# Schem_WS_v4.net
KiCad netlist of a schematic drawn in Altium Designer
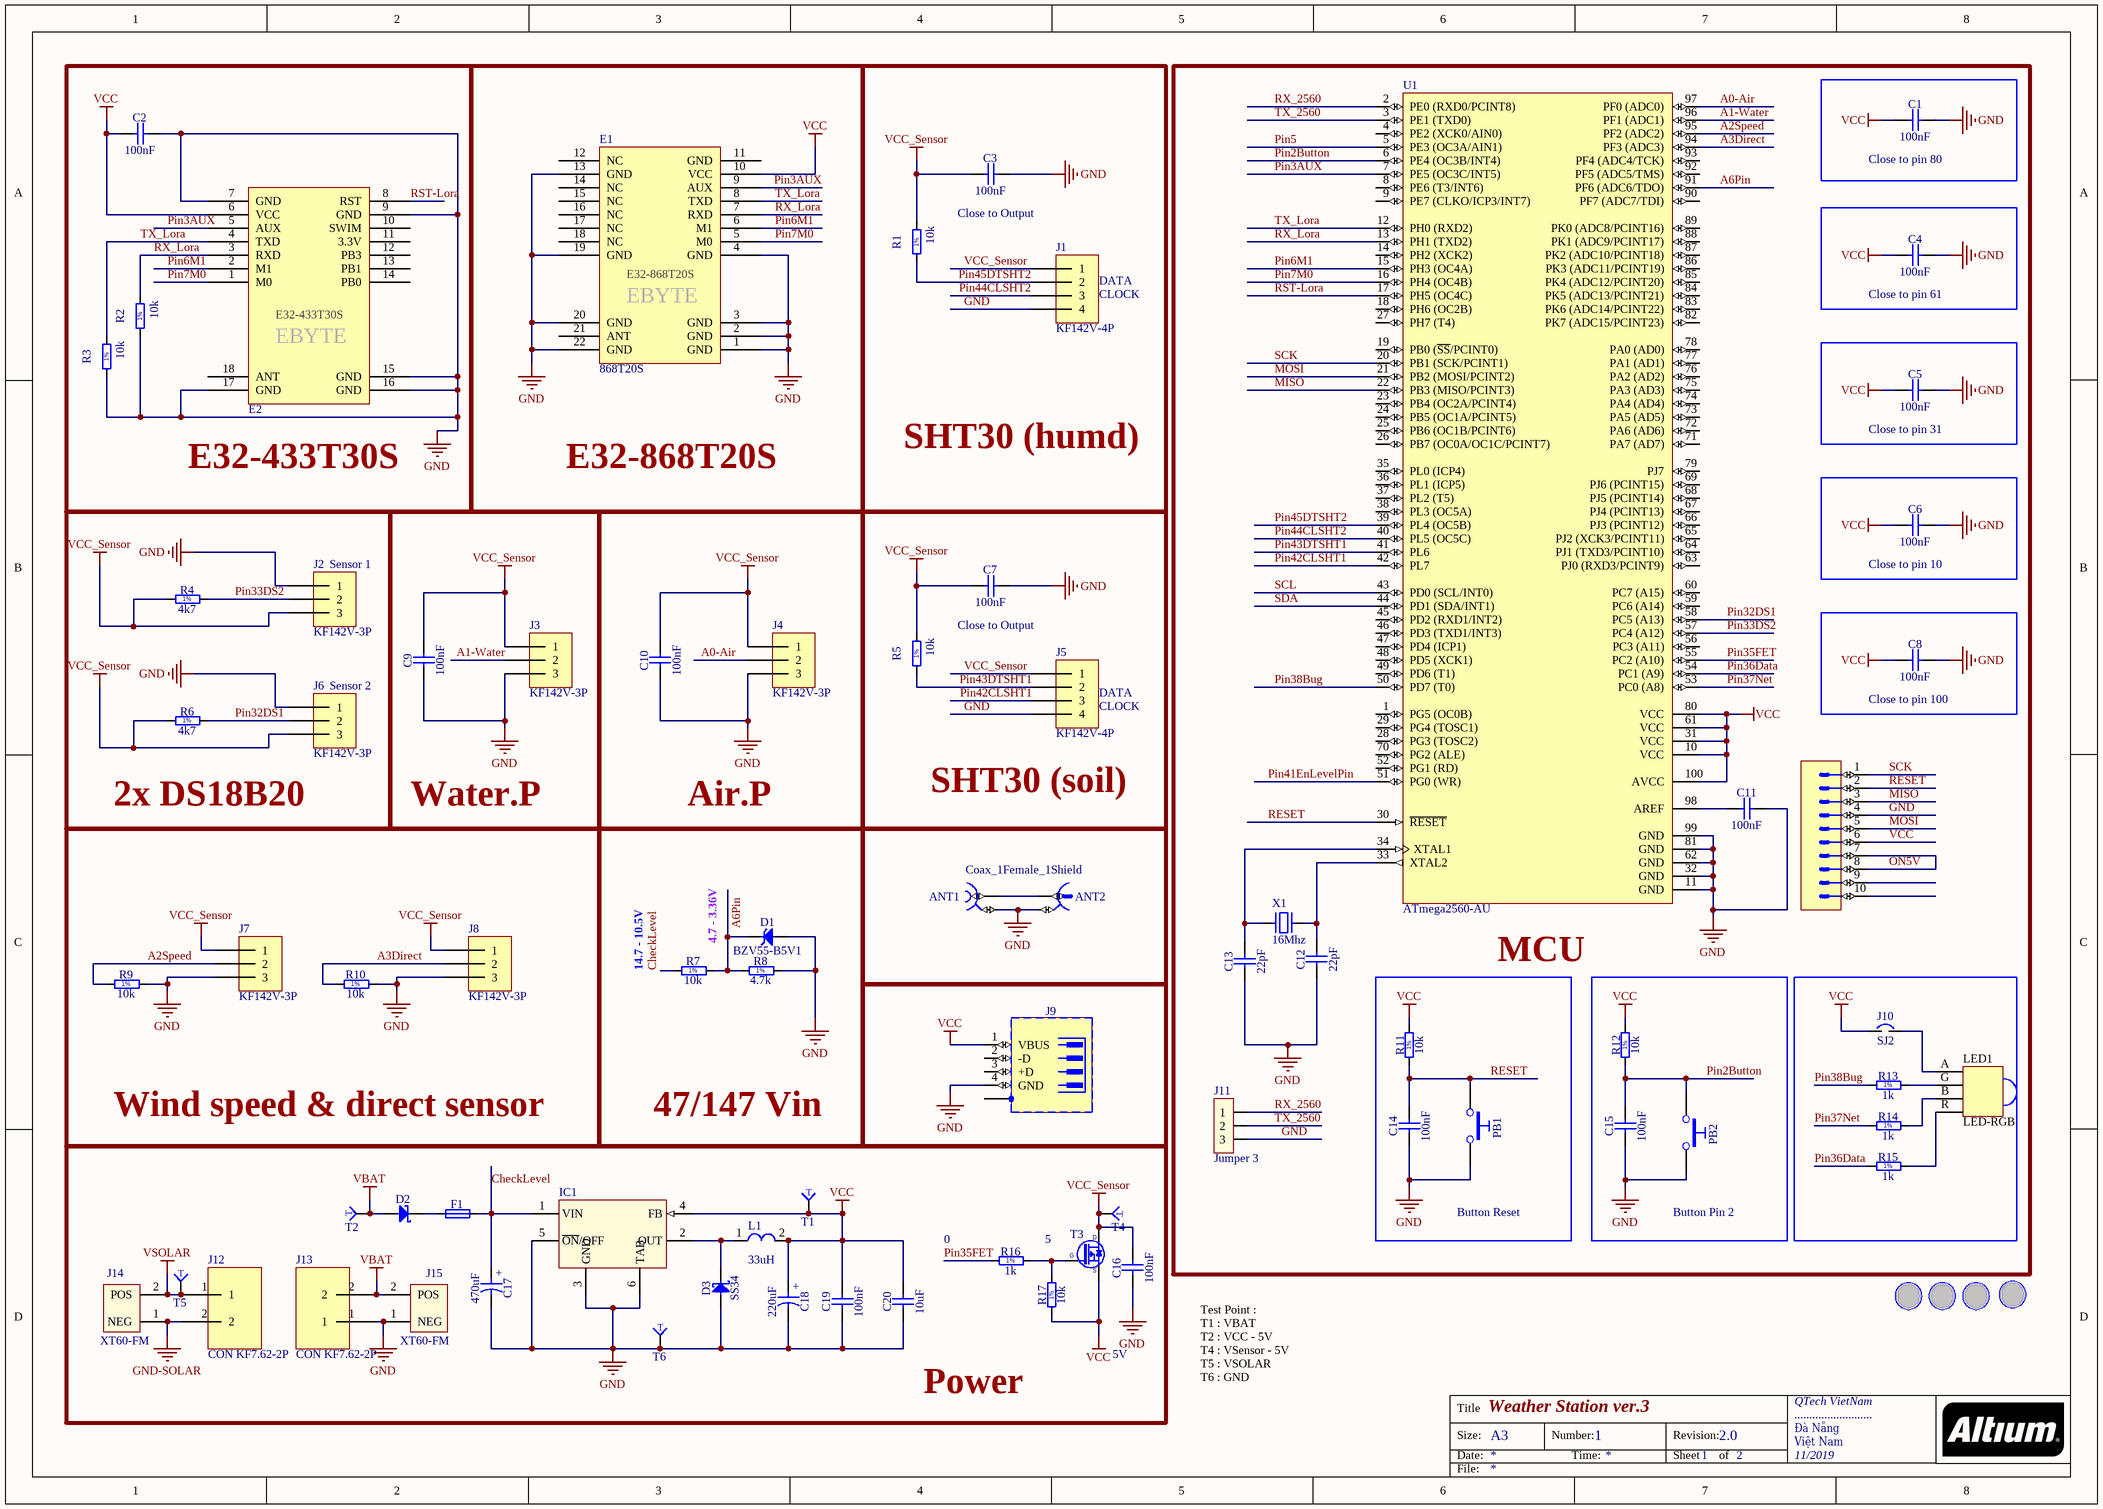
[diagram p0: Schem_WS_v4.SchDoc]

(export (version "E")
  (design (tool "Eeschema 10.0.6"))
  (components
    (comp (ref "ANT1")
      (value "Coax_1Female_1Shield")
      (footprint "HUBER-SUHNER_85 SMA-50-0-101/111 NE")
      (fields
        (field (name "PART NUMBER") "HUBER-SUHNER_85_SMA-50-0-101/111_NE")
        (field (name "MANUFACTURER") "HUBER+SUHNER")
        (field (name "MANUFACTURER PART NUMBER") "85_SMA-50-0-101/111_NE")
      )
      (libsource (lib "Connectors") (part "Coax_1Female_1Shield"))
    )
    (comp (ref "ANT2")
      (value "U.FL")
      (footprint "HIROSE_U.FL-R-SMT-1(10)")
      (fields
        (field (name "PART NUMBER") "HIROSE_U.FL-R-SMT-1(10)")
        (field (name "MANUFACTURER") "HIROSE (HRS)")
        (field (name "MANUFACTURER PART NUMBER") "U.FL-R-SMT-1(10)")
      )
      (libsource (lib "Connectors") (part "Coax_1Male_1Shield"))
    )
    (comp (ref "C1")
      (value "100nF")
      (footprint "CAPC1608X87N")
      (description "Non-polarised capacitor")
      (fields (field (name "PART NUMBER") "CC0603_100NF_50V_10%_X7R") (field (name "VOLTAGE") "50V"))
      (libsource (lib "Capacitors") (part "Capacitor - non polarized"))
    )
    (comp (ref "C2")
      (value "100nF")
      (footprint "CAPC1608X87N")
      (description "Non-polarised capacitor")
      (fields (field (name "PART NUMBER") "CC0603_100NF_50V_10%_X7R") (field (name "VOLTAGE") "50V"))
      (libsource (lib "Capacitors") (part "Capacitor - non polarized"))
    )
    (comp (ref "C3")
      (value "100nF")
      (footprint "CAPC1608X87N")
      (description "Non-polarised capacitor")
      (fields (field (name "PART NUMBER") "CC0603_100NF_50V_10%_X7R") (field (name "VOLTAGE") "50V"))
      (libsource (lib "Capacitors") (part "Capacitor - non polarized"))
    )
    (comp (ref "C4")
      (value "100nF")
      (footprint "CAPC1608X87N")
      (description "Non-polarised capacitor")
      (fields (field (name "PART NUMBER") "CC0603_100NF_50V_10%_X7R") (field (name "VOLTAGE") "50V"))
      (libsource (lib "Capacitors") (part "Capacitor - non polarized"))
    )
    (comp (ref "C5")
      (value "100nF")
      (footprint "CAPC1608X87N")
      (description "Non-polarised capacitor")
      (fields (field (name "PART NUMBER") "CC0603_100NF_50V_10%_X7R") (field (name "VOLTAGE") "50V"))
      (libsource (lib "Capacitors") (part "Capacitor - non polarized"))
    )
    (comp (ref "C6")
      (value "100nF")
      (footprint "CAPC1608X87N")
      (description "Non-polarised capacitor")
      (fields (field (name "PART NUMBER") "CC0603_100NF_50V_10%_X7R") (field (name "VOLTAGE") "50V"))
      (libsource (lib "Capacitors") (part "Capacitor - non polarized"))
    )
    (comp (ref "C7")
      (value "100nF")
      (footprint "CAPC1608X87N")
      (description "Non-polarised capacitor")
      (fields (field (name "PART NUMBER") "CC0603_100NF_50V_10%_X7R") (field (name "VOLTAGE") "50V"))
      (libsource (lib "Capacitors") (part "Capacitor - non polarized"))
    )
    (comp (ref "C8")
      (value "100nF")
      (footprint "CAPC1608X87N")
      (description "Non-polarised capacitor")
      (fields (field (name "PART NUMBER") "CC0603_100NF_50V_10%_X7R") (field (name "VOLTAGE") "50V"))
      (libsource (lib "Capacitors") (part "Capacitor - non polarized"))
    )
    (comp (ref "C9")
      (value "100nF")
      (footprint "CAPC1608X87N")
      (description "Non-polarised capacitor")
      (fields (field (name "PART NUMBER") "CC0603_100NF_50V_10%_X7R") (field (name "VOLTAGE") "50V"))
      (libsource (lib "Capacitors") (part "Capacitor - non polarized"))
    )
    (comp (ref "C10")
      (value "100nF")
      (footprint "CAPC1608X87N")
      (description "Non-polarised capacitor")
      (fields (field (name "PART NUMBER") "CC0603_100NF_50V_10%_X7R") (field (name "VOLTAGE") "50V"))
      (libsource (lib "Capacitors") (part "Capacitor - non polarized"))
    )
    (comp (ref "C11")
      (value "100nF")
      (footprint "CAPC1608X87N")
      (description "Non-polarised capacitor")
      (fields (field (name "PART NUMBER") "CC0603_100NF_50V_10%_X7R") (field (name "VOLTAGE") "50V"))
      (libsource (lib "Capacitors") (part "Capacitor - non polarized"))
    )
    (comp (ref "C12")
      (value "22pF")
      (footprint "CAPC1608X87N")
      (description "Non-polarised capacitor")
      (fields (field (name "PART NUMBER") "CC0603_22PF_50V_5%_NP0") (field (name "VOLTAGE") "50V"))
      (libsource (lib "Capacitors") (part "Capacitor - non polarized"))
    )
    (comp (ref "C13")
      (value "22pF")
      (footprint "CAPC1608X87N")
      (description "Non-polarised capacitor")
      (fields (field (name "PART NUMBER") "CC0603_22PF_50V_5%_NP0") (field (name "VOLTAGE") "50V"))
      (libsource (lib "Capacitors") (part "Capacitor - non polarized"))
    )
    (comp (ref "C14")
      (value "100nF")
      (footprint "CAPC1608X87N")
      (description "Non-polarised capacitor")
      (fields (field (name "PART NUMBER") "CC0603_100NF_50V_10%_X7R") (field (name "VOLTAGE") "50V"))
      (libsource (lib "Capacitors") (part "Capacitor - non polarized"))
    )
    (comp (ref "C15")
      (value "100nF")
      (footprint "CAPC1608X87N")
      (description "Non-polarised capacitor")
      (fields (field (name "PART NUMBER") "CC0603_100NF_50V_10%_X7R") (field (name "VOLTAGE") "50V"))
      (libsource (lib "Capacitors") (part "Capacitor - non polarized"))
    )
    (comp (ref "C16")
      (value "100nF")
      (footprint "CAPC1608X87N")
      (description "Non-polarised capacitor")
      (fields (field (name "PART NUMBER") "CC0603_100NF_50V_10%_X7R") (field (name "VOLTAGE") "50V"))
      (libsource (lib "Capacitors") (part "Capacitor - non polarized"))
    )
    (comp (ref "C17")
      (value "470uF")
      (footprint "CAPAE1030X1020N")
      (description "Polarised capacitor")
      (fields (field (name "PART NUMBER") "CAE1030-1020_470UF_25V_20%") (field (name "VOLTAGE") "25V"))
      (libsource (lib "Capacitors") (part "Capacitor - polarized"))
    )
    (comp (ref "C18")
      (value "220uF")
      (footprint "CAPMP6032X280N")
      (description "Polarised capacitor")
      (fields
        (field (name "PART NUMBER") "CTE6032-28_100UF_6.3V_10%_LESR0075")
        (field (name "VOLTAGE") "6.3V")
      )
      (libsource (lib "Capacitors") (part "Capacitor - polarized"))
    )
    (comp (ref "C19")
      (value "100nF")
      (footprint "CAPC1608X87N")
      (description "Non-polarised capacitor")
      (fields (field (name "PART NUMBER") "CC0603_100NF_50V_10%_X7R") (field (name "VOLTAGE") "50V"))
      (libsource (lib "Capacitors") (part "Capacitor - non polarized"))
    )
    (comp (ref "C20")
      (value "10uF")
      (footprint "CAPC2012X135N")
      (description "Non-polarised capacitor")
      (fields (field (name "PART NUMBER") "CC0805_10UF_16V_10%_X5R") (field (name "VOLTAGE") "16V"))
      (libsource (lib "Capacitors") (part "Capacitor - non polarized"))
    )
    (comp (ref "D1")
      (value "BZV55-B5V1")
      (footprint "DIOMELF3515N")
      (description "Zener Diode")
      (fields (field (name "VOLTAGE") "5V1") (field (name "POWER") "500mW"))
      (libsource (lib "ICs And Semiconductors") (part "Diode Zener"))
    )
    (comp (ref "D2")
      (value "SS16")
      (footprint "DIOM5127X229N")
      (description "Schottky Diode")
      (fields (field (name "VOLTAGE") "60V") (field (name "POWER") "1A"))
      (libsource (lib "ICs And Semiconductors") (part "Diode Schottky"))
    )
    (comp (ref "D3")
      (value "SS34")
      (footprint "DIOM5127X229N")
      (description "Schottky Diode")
      (fields (field (name "PART NUMBER") "SS16") (field (name "VOLTAGE") "60V"))
      (libsource (lib "ICs And Semiconductors") (part "Diode Schottky"))
    )
    (comp (ref "E1")
      (value "868T20S")
      (footprint "E32-T20S")
      (description "Lora Ebyte E32-T30S Module")
      (libsource (lib "alib_pnphien") (part "E32-868T20S"))
    )
    (comp (ref "E2")
      (value "E32-T30S")
      (footprint "E32-433T30S")
      (description "Lora Ebyte E32-T30S Module")
      (libsource (lib "alib_pnphien") (part "E32-433T30S"))
    )
    (comp (ref "F1")
      (value "140mA-60V")
      (footprint "FUSRC4632X90N")
      (description "Fuse")
      (fields
        (field (name "PART NUMBER") "FUSR1812_TYCO-MINISMDC014F")
        (field (name "MANUFACTURER") "TYCO ELECTRONICS")
      )
      (libsource (lib "Eletro-mechanical") (part "Fuse"))
    )
    (comp (ref "HOLE1")
      (value "HOLE")
      (footprint "HOLE M3")
      (libsource (lib "alib_pnphien") (part "HOLE M3"))
    )
    (comp (ref "HOLE2")
      (value "HOLE")
      (footprint "HOLE M3")
      (libsource (lib "alib_pnphien") (part "HOLE M3"))
    )
    (comp (ref "HOLE3")
      (value "HOLE")
      (footprint "HOLE M3")
      (libsource (lib "alib_pnphien") (part "HOLE M3"))
    )
    (comp (ref "HOLE4")
      (value "HOLE")
      (footprint "HOLE M3")
      (libsource (lib "alib_pnphien") (part "HOLE M3"))
    )
    (comp (ref "IC1")
      (value "LM2596")
      (footprint "TO263-5")
      (libsource (lib "alib_pnphien") (part "LM2596-5V"))
    )
    (comp (ref "J1")
      (value "KF142V-4P")
      (footprint "CON KF142V-4P-5.08")
      (description "CON KF142V-4P-5.08")
      (libsource (lib "alib_pnphien") (part "CON KF142V-4P-5.08"))
    )
    (comp (ref "J2")
      (value "KF142V-3P")
      (footprint "CON KF142V-3P-5.08")
      (description "CON KF142V-3P-5.08")
      (libsource (lib "alib_pnphien") (part "CON KF142V-3P-5.08"))
    )
    (comp (ref "J3")
      (value "KF142V-3P")
      (footprint "CON KF142V-3P-5.08")
      (description "CON KF142V-3P-5.08")
      (libsource (lib "alib_pnphien") (part "CON KF142V-3P-5.08"))
    )
    (comp (ref "J4")
      (value "KF142V-3P")
      (footprint "CON KF142V-3P-5.08")
      (description "CON KF142V-3P-5.08")
      (libsource (lib "alib_pnphien") (part "CON KF142V-3P-5.08"))
    )
    (comp (ref "J5")
      (value "KF142V-4P")
      (footprint "CON KF142V-4P-5.08")
      (description "CON KF142V-4P-5.08")
      (libsource (lib "alib_pnphien") (part "CON KF142V-4P-5.08"))
    )
    (comp (ref "J6")
      (value "KF142V-3P")
      (footprint "CON KF142V-3P-5.08")
      (description "CON KF142V-3P-5.08")
      (libsource (lib "alib_pnphien") (part "CON KF142V-3P-5.08"))
    )
    (comp (ref "J7")
      (value "KF142V-3P")
      (footprint "CON KF142V-3P-5.08")
      (description "CON KF142V-3P-5.08")
      (libsource (lib "alib_pnphien") (part "CON KF142V-3P-5.08"))
    )
    (comp (ref "J8")
      (value "KF142V-3P")
      (footprint "CON KF142V-3P-5.08")
      (description "CON KF142V-3P-5.08")
      (libsource (lib "alib_pnphien") (part "CON KF142V-3P-5.08"))
    )
    (comp (ref "J9")
      (value "USB")
      (footprint "FCI_87520-0010BLF")
      (description "4 Pin + 1 Shield USB Receptacle")
      (fields (field (name "PART NUMBER") "FCI_87520-0010BLF") (field (name "MANUFACTURER") "FCI"))
      (libsource (lib "Connectors") (part "Connector USB 4 Pin + 1Shield"))
    )
    (comp (ref "J10")
      (value "SJ2")
      (footprint "SJ2")
      (description "Solder Jump2")
      (libsource (lib "sdc") (part "SJ2"))
    )
    (comp (ref "J11") (value "Jumper 3") (footprint "JP3") (libsource (lib "syhaunguyen") (part "JP3")))
    (comp (ref "J12")
      (value "CON KF7.62-2P")
      (footprint "CON KF7.62-2P")
      (libsource (lib "alib_pnphien") (part "CON KF7.62-2P"))
    )
    (comp (ref "J13")
      (value "CON KF7.62-2P")
      (footprint "CON KF7.62-2P")
      (libsource (lib "") (part "CON KF7.62-2P_1"))
    )
    (comp (ref "J14")
      (value "XT60-FM")
      (footprint "XT60-FM")
      (fields (field (name "MF") "AMASS") (field (name "MP") "XT60-M"))
      (libsource (lib "alib_pnphien") (part "XT60-FM"))
    )
    (comp (ref "J15")
      (value "XT60-FM")
      (footprint "XT60-FM")
      (fields (field (name "MF") "AMASS") (field (name "MP") "XT60-M"))
      (libsource (lib "") (part "XT60-FM_1"))
    )
    (comp (ref "JTAG1")
      (value "Header 10")
      (footprint "3M_N2510-6002RB")
      (description "Connector 10 Male")
      (fields (field (name "PART NUMBER") "3M_N2510-6002RB") (field (name "MANUFACTURER") "3M"))
      (libsource (lib "Connectors") (part "Connector 10 Male"))
    )
    (comp (ref "L1") (value "33uH") (footprint "L_SMD") (libsource (lib "sdc") (part "L_SMD 33uH")))
    (comp (ref "LED1")
      (value "LED-RGB")
      (footprint "LED-5MMRGBCA")
      (libsource (lib "LIBRARY") (part "LED-RGB"))
    )
    (comp (ref "PB1")
      (value "Push Button")
      (footprint "PB_TYCO_FSMSM")
      (description "Push-Button Switch SPDT")
      (fields (field (name "PART NUMBER") "PB_TYCO_FSMSM") (field (name "MANUFACTURER") "TYCO ELECTRONICS"))
      (libsource (lib "sdc") (part "PB SPST 1NO-2NO"))
    )
    (comp (ref "PB2")
      (value "Push Button")
      (footprint "PB_TYCO_FSMSM")
      (description "Push-Button Switch SPDT")
      (fields (field (name "PART NUMBER") "PB_TYCO_FSMSM") (field (name "MANUFACTURER") "TYCO ELECTRONICS"))
      (libsource (lib "sdc") (part "PB SPST 1NO-2NO"))
    )
    (comp (ref "R1")
      (value "10k")
      (footprint "RESC1608X55N")
      (description "Resistor - 1%")
      (fields (field (name "PART NUMBER") "R0603_10K_1%_0.1W_100PPM") (field (name "POWER") "0.1W"))
      (libsource (lib "Resistors") (part "Resistor - 1%"))
    )
    (comp (ref "R2")
      (value "10k")
      (footprint "RESC1608X55N")
      (description "Resistor - 1%")
      (fields (field (name "PART NUMBER") "R0603_10K_1%_0.1W_100PPM") (field (name "POWER") "0.1W"))
      (libsource (lib "Resistors") (part "Resistor - 1%"))
    )
    (comp (ref "R3")
      (value "10k")
      (footprint "RESC1608X55N")
      (description "Resistor - 1%")
      (fields (field (name "PART NUMBER") "R0603_10K_1%_0.1W_100PPM") (field (name "POWER") "0.1W"))
      (libsource (lib "Resistors") (part "Resistor - 1%"))
    )
    (comp (ref "R4")
      (value "4k7")
      (footprint "RESC1608X55N")
      (description "Resistor - 1%")
      (fields (field (name "PART NUMBER") "R0603_4K7_1%_0.1W_100PPM") (field (name "POWER") "0.1W"))
      (libsource (lib "Resistors") (part "Resistor - 1%"))
    )
    (comp (ref "R5")
      (value "10k")
      (footprint "RESC1608X55N")
      (description "Resistor - 1%")
      (fields (field (name "PART NUMBER") "R0603_10K_1%_0.1W_100PPM") (field (name "POWER") "0.1W"))
      (libsource (lib "Resistors") (part "Resistor - 1%"))
    )
    (comp (ref "R6")
      (value "4k7")
      (footprint "RESC1608X55N")
      (description "Resistor - 1%")
      (fields (field (name "PART NUMBER") "R0603_4K7_1%_0.1W_100PPM") (field (name "POWER") "0.1W"))
      (libsource (lib "Resistors") (part "Resistor - 1%"))
    )
    (comp (ref "R7")
      (value "10k")
      (footprint "RESC1608X55N")
      (description "Resistor - 1%")
      (fields (field (name "PART NUMBER") "R0603_2M_1%_0.1W_100PPM") (field (name "POWER") "0.1W"))
      (libsource (lib "Resistors") (part "Resistor - 1%"))
    )
    (comp (ref "R8")
      (value "4.7k")
      (footprint "RESC1608X55N")
      (description "Resistor - 1%")
      (fields (field (name "PART NUMBER") "R0603_1M_1%_0.1W_100PPM") (field (name "POWER") "0.1W"))
      (libsource (lib "Resistors") (part "Resistor - 1%"))
    )
    (comp (ref "R9")
      (value "10k")
      (footprint "RESC1608X55N")
      (description "Resistor - 1%")
      (fields (field (name "PART NUMBER") "R0603_160R_1%_0.1W_100PPM") (field (name "POWER") "0.1W"))
      (libsource (lib "Resistors") (part "Resistor - 1%"))
    )
    (comp (ref "R10")
      (value "10k")
      (footprint "RESC1608X55N")
      (description "Resistor - 1%")
      (fields (field (name "PART NUMBER") "R0603_160R_1%_0.1W_100PPM") (field (name "POWER") "0.1W"))
      (libsource (lib "Resistors") (part "Resistor - 1%"))
    )
    (comp (ref "R11")
      (value "10k")
      (footprint "RESC1608X55N")
      (description "Resistor - 1%")
      (fields (field (name "PART NUMBER") "R0603_10K_1%_0.1W_100PPM") (field (name "POWER") "0.1W"))
      (libsource (lib "Resistors") (part "Resistor - 1%"))
    )
    (comp (ref "R12")
      (value "10k")
      (footprint "RESC1608X55N")
      (description "Resistor - 1%")
      (fields (field (name "PART NUMBER") "R0603_10K_1%_0.1W_100PPM") (field (name "POWER") "0.1W"))
      (libsource (lib "Resistors") (part "Resistor - 1%"))
    )
    (comp (ref "R13")
      (value "1k")
      (footprint "RESC1608X55N")
      (description "Resistor - 1%")
      (fields (field (name "PART NUMBER") "R0603_1K_1%_0.1W_100PPM") (field (name "POWER") "0.1W"))
      (libsource (lib "Resistors") (part "Resistor - 1%"))
    )
    (comp (ref "R14")
      (value "1k")
      (footprint "RESC1608X55N")
      (description "Resistor - 1%")
      (fields (field (name "PART NUMBER") "R0603_1K_1%_0.1W_100PPM") (field (name "POWER") "0.1W"))
      (libsource (lib "Resistors") (part "Resistor - 1%"))
    )
    (comp (ref "R15")
      (value "1k")
      (footprint "RESC1608X55N")
      (description "Resistor - 1%")
      (fields (field (name "PART NUMBER") "R0603_1K_1%_0.1W_100PPM") (field (name "POWER") "0.1W"))
      (libsource (lib "Resistors") (part "Resistor - 1%"))
    )
    (comp (ref "R16")
      (value "1k")
      (footprint "RESC1608X55N")
      (description "Resistor - 1%")
      (fields (field (name "PART NUMBER") "R0603_1K_1%_0.1W_100PPM") (field (name "POWER") "0.1W"))
      (libsource (lib "Resistors") (part "Resistor - 1%"))
    )
    (comp (ref "R17")
      (value "10k")
      (footprint "RESC1608X55N")
      (description "Resistor - 1%")
      (fields (field (name "PART NUMBER") "R0603_10K_1%_0.1W_100PPM") (field (name "POWER") "0.1W"))
      (libsource (lib "Resistors") (part "Resistor - 1%"))
    )
    (comp (ref "T1")
      (value "Test Point")
      (footprint "TP1x1r")
      (description "Test Point Round 1x1 mm")
      (libsource (lib "alib_pnphien") (part "TP R1x1"))
    )
    (comp (ref "T2")
      (value "Test Point")
      (footprint "TP1x1r")
      (description "Test Point Round 1x1 mm")
      (libsource (lib "alib_pnphien") (part "TP R1x1"))
    )
    (comp (ref "T3")
      (value "BSH203")
      (footprint "SOT95P230X110-3N")
      (description "P-CHANNEL MOSFET WITH DIODE")
      (fields (field (name "MANUFACTURER") "NXP SEMICONDUCTORS"))
      (libsource (lib "ICs And Semiconductors") (part "P-MOSFET-D 1G 2S 3D"))
    )
    (comp (ref "T4")
      (value "Test Point")
      (footprint "TP1x1r")
      (description "Test Point Round 1x1 mm")
      (libsource (lib "alib_pnphien") (part "TP R1x1"))
    )
    (comp (ref "T5")
      (value "Test Point")
      (footprint "TP1x1r")
      (description "Test Point Round 1x1 mm")
      (libsource (lib "alib_pnphien") (part "TP R1x1"))
    )
    (comp (ref "T6")
      (value "Test Point")
      (footprint "TP1x1r")
      (description "Test Point Round 1x1 mm")
      (libsource (lib "alib_pnphien") (part "TP R1x1"))
    )
    (comp (ref "U1")
      (value "ATmega2560-AU")
      (footprint "TQFP100L")
      (libsource (lib "LIBRARY") (part "ATmega2560-AU"))
    )
    (comp (ref "X1")
      (value "16Mhz")
      (footprint "XT2")
      (description "Crystal, 32.768 KHz, -40 to 85 degC, 3.2 x 1.5 x 0.9 mm SMD")
      (libsource (lib "LIBRARY") (part "XT2"))
    )
  )
  (nets
    (net (code "1") (name "/A0-Air") (class "Default")
      (node (ref "J4") (pin "2") (pinfunction "2_2") (pintype "passive"))
      (node (ref "U1") (pin "97") (pinfunction "PF0_(ADC0)_97") (pintype "bidirectional"))
    )
    (net (code "2") (name "/A1-Water") (class "Default")
      (node (ref "J3") (pin "2") (pinfunction "2_2") (pintype "passive"))
      (node (ref "U1") (pin "96") (pinfunction "PF1_(ADC1)_96") (pintype "bidirectional"))
    )
    (net (code "3") (name "/A2Speed") (class "Default")
      (node (ref "J7") (pin "2") (pinfunction "2_2") (pintype "passive"))
      (node (ref "R9") (pin "1") (pinfunction "1_1") (pintype "passive"))
      (node (ref "U1") (pin "95") (pinfunction "PF2_(ADC2)_95") (pintype "bidirectional"))
    )
    (net (code "4") (name "/A3Direct") (class "Default")
      (node (ref "J8") (pin "2") (pinfunction "2_2") (pintype "passive"))
      (node (ref "R10") (pin "1") (pinfunction "1_1") (pintype "passive"))
      (node (ref "U1") (pin "94") (pinfunction "PF3_(ADC3)_94") (pintype "bidirectional"))
    )
    (net (code "5") (name "/A6Pin") (class "Default")
      (node (ref "D1") (pin "1") (pinfunction "C_1") (pintype "passive"))
      (node (ref "R7") (pin "2") (pinfunction "2_2") (pintype "passive"))
      (node (ref "R8") (pin "1") (pinfunction "1_1") (pintype "passive"))
      (node (ref "U1") (pin "91") (pinfunction "PF6_(ADC6/TDO)_91") (pintype "bidirectional"))
    )
    (net (code "6") (name "/CheckLevel") (class "Default")
      (node (ref "C17") (pin "1") (pinfunction "1_1") (pintype "passive"))
      (node (ref "F1") (pin "2") (pinfunction "2_2") (pintype "passive"))
      (node (ref "IC1") (pin "1") (pinfunction "VIN_1") (pintype "passive"))
      (node (ref "R7") (pin "1") (pinfunction "1_1") (pintype "passive"))
    )
    (net (code "7") (name "/MISO") (class "Default")
      (node (ref "JTAG1") (pin "3") (pinfunction "3_3") (pintype "bidirectional"))
      (node (ref "U1") (pin "22") (pinfunction "PB3_(MISO/PCINT3)_22") (pintype "bidirectional"))
    )
    (net (code "8") (name "/MOSI") (class "Default")
      (node (ref "JTAG1") (pin "5") (pinfunction "5_5") (pintype "bidirectional"))
      (node (ref "U1") (pin "21") (pinfunction "PB2_(MOSI/PCINT2)_21") (pintype "bidirectional"))
    )
    (net (code "9") (name "/ON5V") (class "Default")
      (node (ref "JTAG1") (pin "7") (pinfunction "7_7") (pintype "bidirectional"))
      (node (ref "JTAG1") (pin "8") (pinfunction "8_8") (pintype "bidirectional"))
    )
    (net (code "10") (name "/Pin2Button") (class "Default")
      (node (ref "C15") (pin "2") (pinfunction "2_2") (pintype "passive"))
      (node (ref "PB2") (pin "1") (pinfunction "1_1") (pintype "passive"))
      (node (ref "R12") (pin "1") (pinfunction "1_1") (pintype "passive"))
      (node (ref "U1") (pin "6") (pinfunction "PE4_(OC3B/INT4)_6") (pintype "bidirectional"))
    )
    (net (code "11") (name "/Pin3AUX") (class "Default")
      (node (ref "E1") (pin "9") (pinfunction "AUX_9") (pintype "passive"))
      (node (ref "E2") (pin "5") (pinfunction "AUX_5") (pintype "passive"))
      (node (ref "U1") (pin "7") (pinfunction "PE5_(OC3C/INT5)_7") (pintype "bidirectional"))
    )
    (net (code "12") (name "/Pin5") (class "Default")
      (node (ref "U1") (pin "5") (pinfunction "PE3_(OC3A/AIN1)_5") (pintype "bidirectional"))
    )
    (net (code "13") (name "/Pin6M1") (class "Default")
      (node (ref "E1") (pin "6") (pinfunction "M1_6") (pintype "passive"))
      (node (ref "E2") (pin "2") (pinfunction "M1_2") (pintype "passive"))
      (node (ref "U1") (pin "15") (pinfunction "PH3_(OC4A)_15") (pintype "bidirectional"))
    )
    (net (code "14") (name "/Pin7M0") (class "Default")
      (node (ref "E1") (pin "5") (pinfunction "M0_5") (pintype "passive"))
      (node (ref "E2") (pin "1") (pinfunction "M0_1") (pintype "passive"))
      (node (ref "U1") (pin "16") (pinfunction "PH4_(OC4B)_16") (pintype "bidirectional"))
    )
    (net (code "15") (name "/Pin32DS1") (class "Default")
      (node (ref "J6") (pin "2") (pinfunction "2_2") (pintype "passive"))
      (node (ref "R6") (pin "2") (pinfunction "2_2") (pintype "passive"))
      (node (ref "U1") (pin "58") (pinfunction "PC5_(A13)_58") (pintype "bidirectional"))
    )
    (net (code "16") (name "/Pin33DS2") (class "Default")
      (node (ref "J2") (pin "2") (pinfunction "2_2") (pintype "passive"))
      (node (ref "R4") (pin "2") (pinfunction "2_2") (pintype "passive"))
      (node (ref "U1") (pin "57") (pinfunction "PC4_(A12)_57") (pintype "bidirectional"))
    )
    (net (code "17") (name "/Pin35FET") (class "Default")
      (node (ref "R16") (pin "1") (pinfunction "1_1") (pintype "passive"))
      (node (ref "U1") (pin "55") (pinfunction "PC2_(A10)_55") (pintype "bidirectional"))
    )
    (net (code "18") (name "/Pin36Data") (class "Default")
      (node (ref "R15") (pin "1") (pinfunction "1_1") (pintype "passive"))
      (node (ref "U1") (pin "54") (pinfunction "PC1_(A9)_54") (pintype "bidirectional"))
    )
    (net (code "19") (name "/Pin37Net") (class "Default")
      (node (ref "R14") (pin "1") (pinfunction "1_1") (pintype "passive"))
      (node (ref "U1") (pin "53") (pinfunction "PC0_(A8)_53") (pintype "bidirectional"))
    )
    (net (code "20") (name "/Pin38Bug") (class "Default")
      (node (ref "R13") (pin "1") (pinfunction "1_1") (pintype "passive"))
      (node (ref "U1") (pin "50") (pinfunction "PD7_(T0)_50") (pintype "bidirectional"))
    )
    (net (code "21") (name "/Pin41EnLevelPin") (class "Default")
      (node (ref "U1") (pin "51") (pinfunction "PG0_(WR)_51") (pintype "bidirectional"))
    )
    (net (code "22") (name "/Pin42CLSHT1") (class "Default")
      (node (ref "J5") (pin "3") (pinfunction "3_3") (pintype "passive"))
      (node (ref "U1") (pin "42") (pinfunction "PL7_42") (pintype "bidirectional"))
    )
    (net (code "23") (name "/Pin43DTSHT1") (class "Default")
      (node (ref "J5") (pin "2") (pinfunction "2_2") (pintype "passive"))
      (node (ref "R5") (pin "1") (pinfunction "1_1") (pintype "passive"))
      (node (ref "U1") (pin "41") (pinfunction "PL6_41") (pintype "bidirectional"))
    )
    (net (code "24") (name "/Pin44CLSHT2") (class "Default")
      (node (ref "J1") (pin "3") (pinfunction "3_3") (pintype "passive"))
      (node (ref "U1") (pin "40") (pinfunction "PL5_(OC5C)_40") (pintype "bidirectional"))
    )
    (net (code "25") (name "/Pin45DTSHT2") (class "Default")
      (node (ref "J1") (pin "2") (pinfunction "2_2") (pintype "passive"))
      (node (ref "R1") (pin "1") (pinfunction "1_1") (pintype "passive"))
      (node (ref "U1") (pin "39") (pinfunction "PL4_(OC5B)_39") (pintype "bidirectional"))
    )
    (net (code "26") (name "/RESET") (class "Default")
      (node (ref "C14") (pin "2") (pinfunction "2_2") (pintype "passive"))
      (node (ref "JTAG1") (pin "2") (pinfunction "2_2") (pintype "bidirectional"))
      (node (ref "PB1") (pin "1") (pinfunction "1_1") (pintype "passive"))
      (node (ref "R11") (pin "1") (pinfunction "1_1") (pintype "passive"))
      (node (ref "U1") (pin "30") (pinfunction "~{RESET}_30") (pintype "input"))
    )
    (net (code "27") (name "/RST-Lora") (class "Default")
      (node (ref "E2") (pin "8") (pinfunction "RST_8") (pintype "passive"))
      (node (ref "U1") (pin "17") (pinfunction "PH5_(OC4C)_17") (pintype "bidirectional"))
    )
    (net (code "28") (name "/RX_2560") (class "Default")
      (node (ref "J11") (pin "1") (pinfunction "1_1") (pintype "passive"))
      (node (ref "U1") (pin "2") (pinfunction "PE0_(RXD0/PCINT8)_2") (pintype "bidirectional"))
    )
    (net (code "29") (name "/RX_Lora") (class "Default")
      (node (ref "E1") (pin "7") (pinfunction "RXD_7") (pintype "passive"))
      (node (ref "E2") (pin "3") (pinfunction "RXD_3") (pintype "passive"))
      (node (ref "R2") (pin "2") (pinfunction "2_2") (pintype "passive"))
      (node (ref "U1") (pin "13") (pinfunction "PH1_(TXD2)_13") (pintype "bidirectional"))
    )
    (net (code "30") (name "/SCK") (class "Default")
      (node (ref "JTAG1") (pin "1") (pinfunction "1_1") (pintype "bidirectional"))
      (node (ref "U1") (pin "20") (pinfunction "PB1_(SCK/PCINT1)_20") (pintype "bidirectional"))
    )
    (net (code "31") (name "/SCL") (class "Default")
      (node (ref "U1") (pin "43") (pinfunction "PD0_(SCL/INT0)_43") (pintype "bidirectional"))
    )
    (net (code "32") (name "/SDA") (class "Default")
      (node (ref "U1") (pin "44") (pinfunction "PD1_(SDA/INT1)_44") (pintype "bidirectional"))
    )
    (net (code "33") (name "/TX_2560") (class "Default")
      (node (ref "J11") (pin "2") (pinfunction "2_2") (pintype "passive"))
      (node (ref "U1") (pin "3") (pinfunction "PE1_(TXD0)_3") (pintype "bidirectional"))
    )
    (net (code "34") (name "/TX_Lora") (class "Default")
      (node (ref "E1") (pin "8") (pinfunction "TXD_8") (pintype "passive"))
      (node (ref "E2") (pin "4") (pinfunction "TXD_4") (pintype "passive"))
      (node (ref "R3") (pin "2") (pinfunction "2_2") (pintype "passive"))
      (node (ref "U1") (pin "12") (pinfunction "PH0_(RXD2)_12") (pintype "bidirectional"))
    )
    (net (code "35") (name "GND") (class "Default")
      (node (ref "ANT1") (pin "2") (pinfunction "2_2") (pintype "bidirectional"))
      (node (ref "ANT2") (pin "2") (pinfunction "2_2") (pintype "bidirectional"))
      (node (ref "C1") (pin "2") (pinfunction "2_2") (pintype "passive"))
      (node (ref "C10") (pin "1") (pinfunction "1_1") (pintype "passive"))
      (node (ref "C11") (pin "2") (pinfunction "2_2") (pintype "passive"))
      (node (ref "C12") (pin "1") (pinfunction "1_1") (pintype "passive"))
      (node (ref "C13") (pin "1") (pinfunction "1_1") (pintype "passive"))
      (node (ref "C14") (pin "1") (pinfunction "1_1") (pintype "passive"))
      (node (ref "C15") (pin "1") (pinfunction "1_1") (pintype "passive"))
      (node (ref "C16") (pin "1") (pinfunction "1_1") (pintype "passive"))
      (node (ref "C17") (pin "2") (pinfunction "2_2") (pintype "passive"))
      (node (ref "C18") (pin "2") (pinfunction "2_2") (pintype "passive"))
      (node (ref "C19") (pin "1") (pinfunction "1_1") (pintype "passive"))
      (node (ref "C2") (pin "2") (pinfunction "2_2") (pintype "passive"))
      (node (ref "C20") (pin "1") (pinfunction "1_1") (pintype "passive"))
      (node (ref "C3") (pin "2") (pinfunction "2_2") (pintype "passive"))
      (node (ref "C4") (pin "2") (pinfunction "2_2") (pintype "passive"))
      (node (ref "C5") (pin "2") (pinfunction "2_2") (pintype "passive"))
      (node (ref "C6") (pin "2") (pinfunction "2_2") (pintype "passive"))
      (node (ref "C7") (pin "2") (pinfunction "2_2") (pintype "passive"))
      (node (ref "C8") (pin "2") (pinfunction "2_2") (pintype "passive"))
      (node (ref "C9") (pin "1") (pinfunction "1_1") (pintype "passive"))
      (node (ref "D1") (pin "2") (pinfunction "A_2") (pintype "passive"))
      (node (ref "D3") (pin "2") (pinfunction "A_2") (pintype "passive"))
      (node (ref "E1") (pin "1") (pinfunction "GND_1") (pintype "passive"))
      (node (ref "E1") (pin "13") (pinfunction "GND_13") (pintype "passive"))
      (node (ref "E1") (pin "19") (pinfunction "GND_19") (pintype "passive"))
      (node (ref "E1") (pin "2") (pinfunction "GND_2") (pintype "passive"))
      (node (ref "E1") (pin "20") (pinfunction "GND_20") (pintype "passive"))
      (node (ref "E1") (pin "22") (pinfunction "GND_22") (pintype "passive"))
      (node (ref "E1") (pin "3") (pinfunction "GND_3") (pintype "passive"))
      (node (ref "E1") (pin "4") (pinfunction "GND_4") (pintype "passive"))
      (node (ref "E2") (pin "15") (pinfunction "GND_15") (pintype "passive"))
      (node (ref "E2") (pin "16") (pinfunction "GND_16") (pintype "passive"))
      (node (ref "E2") (pin "17") (pinfunction "GND_17") (pintype "passive"))
      (node (ref "E2") (pin "7") (pinfunction "GND_7") (pintype "passive"))
      (node (ref "E2") (pin "9") (pinfunction "GND_9") (pintype "passive"))
      (node (ref "IC1") (pin "3") (pinfunction "GND_3") (pintype "passive"))
      (node (ref "IC1") (pin "5") (pinfunction "~{ON}/OFF_5") (pintype "passive"))
      (node (ref "IC1") (pin "6") (pinfunction "TAB_6") (pintype "passive"))
      (node (ref "J1") (pin "4") (pinfunction "4_4") (pintype "passive"))
      (node (ref "J11") (pin "3") (pinfunction "3_3") (pintype "passive"))
      (node (ref "J13") (pin "1") (pinfunction "1_1") (pintype "passive"))
      (node (ref "J15") (pin "1") (pinfunction "NEG_1") (pintype "passive"))
      (node (ref "J2") (pin "1") (pinfunction "1_1") (pintype "passive"))
      (node (ref "J3") (pin "3") (pinfunction "3_3") (pintype "passive"))
      (node (ref "J4") (pin "3") (pinfunction "3_3") (pintype "passive"))
      (node (ref "J5") (pin "4") (pinfunction "4_4") (pintype "passive"))
      (node (ref "J6") (pin "1") (pinfunction "1_1") (pintype "passive"))
      (node (ref "J7") (pin "3") (pinfunction "3_3") (pintype "passive"))
      (node (ref "J8") (pin "3") (pinfunction "3_3") (pintype "passive"))
      (node (ref "J9") (pin "4") (pinfunction "GND_4") (pintype "bidirectional"))
      (node (ref "JTAG1") (pin "4") (pinfunction "4_4") (pintype "bidirectional"))
      (node (ref "PB1") (pin "2") (pinfunction "2_2") (pintype "passive"))
      (node (ref "PB2") (pin "2") (pinfunction "2_2") (pintype "passive"))
      (node (ref "R10") (pin "2") (pinfunction "2_2") (pintype "passive"))
      (node (ref "R2") (pin "1") (pinfunction "1_1") (pintype "passive"))
      (node (ref "R3") (pin "1") (pinfunction "1_1") (pintype "passive"))
      (node (ref "R8") (pin "2") (pinfunction "2_2") (pintype "passive"))
      (node (ref "R9") (pin "2") (pinfunction "2_2") (pintype "passive"))
      (node (ref "T6") (pin "1") (pinfunction "1_1") (pintype "passive"))
      (node (ref "U1") (pin "11") (pinfunction "GND_11") (pintype "power_in"))
      (node (ref "U1") (pin "32") (pinfunction "GND_32") (pintype "power_in"))
      (node (ref "U1") (pin "62") (pinfunction "GND_62") (pintype "power_in"))
      (node (ref "U1") (pin "81") (pinfunction "GND_81") (pintype "power_in"))
      (node (ref "U1") (pin "99") (pinfunction "GND_99") (pintype "power_in"))
    )
    (net (code "36") (name "GND-SOLAR") (class "Default")
      (node (ref "J12") (pin "2") (pinfunction "2_2") (pintype "passive"))
      (node (ref "J14") (pin "1") (pinfunction "NEG_1") (pintype "passive"))
    )
    (net (code "37") (name "Net-(ANT1-Pad1)") (class "Default")
      (node (ref "ANT1") (pin "1") (pinfunction "1_1") (pintype "bidirectional"))
      (node (ref "ANT2") (pin "1") (pinfunction "1_1") (pintype "bidirectional"))
    )
    (net (code "38") (name "Net-(D2-C)") (class "Default")
      (node (ref "D2") (pin "1") (pinfunction "C_1") (pintype "passive"))
      (node (ref "F1") (pin "1") (pinfunction "1_1") (pintype "passive"))
    )
    (net (code "39") (name "Net-(D3-C)") (class "Default")
      (node (ref "D3") (pin "1") (pinfunction "C_1") (pintype "passive"))
      (node (ref "IC1") (pin "2") (pinfunction "OUT_2") (pintype "passive"))
      (node (ref "L1") (pin "1") (pinfunction "1_1") (pintype "passive"))
    )
    (net (code "40") (name "Net-(J10-Pad2)") (class "Default")
      (node (ref "J10") (pin "2") (pinfunction "2_2") (pintype "bidirectional"))
      (node (ref "LED1") (pin "A") (pinfunction "A_A") (pintype "passive"))
    )
    (net (code "41") (name "Net-(LED1-PadB)") (class "Default")
      (node (ref "LED1") (pin "B") (pinfunction "B_B") (pintype "passive"))
      (node (ref "R14") (pin "2") (pinfunction "2_2") (pintype "passive"))
    )
    (net (code "42") (name "Net-(LED1-PadG)") (class "Default")
      (node (ref "LED1") (pin "G") (pinfunction "G_G") (pintype "passive"))
      (node (ref "R13") (pin "2") (pinfunction "2_2") (pintype "passive"))
    )
    (net (code "43") (name "Net-(LED1-PadR)") (class "Default")
      (node (ref "LED1") (pin "R") (pinfunction "R_R") (pintype "passive"))
      (node (ref "R15") (pin "2") (pinfunction "2_2") (pintype "passive"))
    )
    (net (code "44") (name "Net-(T3-G)") (class "Default")
      (node (ref "R16") (pin "2") (pinfunction "2_2") (pintype "passive"))
      (node (ref "R17") (pin "2") (pinfunction "2_2") (pintype "passive"))
      (node (ref "T3") (pin "1") (pinfunction "G_1") (pintype "passive"))
    )
    (net (code "45") (name "Net-(U1-AREF)") (class "Default")
      (node (ref "C11") (pin "1") (pinfunction "1_1") (pintype "passive"))
      (node (ref "U1") (pin "98") (pinfunction "AREF_98") (pintype "power_in"))
    )
    (net (code "46") (name "Net-(U1-XTAL1)") (class "Default")
      (node (ref "C13") (pin "2") (pinfunction "2_2") (pintype "passive"))
      (node (ref "U1") (pin "34") (pinfunction "XTAL1_34") (pintype "input"))
      (node (ref "X1") (pin "2") (pinfunction "2_2") (pintype "passive"))
    )
    (net (code "47") (name "Net-(U1-XTAL2)") (class "Default")
      (node (ref "C12") (pin "2") (pinfunction "2_2") (pintype "passive"))
      (node (ref "U1") (pin "33") (pinfunction "XTAL2_33") (pintype "output"))
      (node (ref "X1") (pin "1") (pinfunction "1_1") (pintype "passive"))
    )
    (net (code "48") (name "VBAT") (class "Default")
      (node (ref "D2") (pin "2") (pinfunction "A_2") (pintype "passive"))
      (node (ref "J13") (pin "2") (pinfunction "2_2") (pintype "passive"))
      (node (ref "J15") (pin "2") (pinfunction "POS_2") (pintype "passive"))
      (node (ref "T2") (pin "1") (pinfunction "1_1") (pintype "passive"))
    )
    (net (code "49") (name "VCC") (class "Default")
      (node (ref "C1") (pin "1") (pinfunction "1_1") (pintype "passive"))
      (node (ref "C18") (pin "1") (pinfunction "1_1") (pintype "passive"))
      (node (ref "C19") (pin "2") (pinfunction "2_2") (pintype "passive"))
      (node (ref "C2") (pin "1") (pinfunction "1_1") (pintype "passive"))
      (node (ref "C20") (pin "2") (pinfunction "2_2") (pintype "passive"))
      (node (ref "C4") (pin "1") (pinfunction "1_1") (pintype "passive"))
      (node (ref "C5") (pin "1") (pinfunction "1_1") (pintype "passive"))
      (node (ref "C6") (pin "1") (pinfunction "1_1") (pintype "passive"))
      (node (ref "C8") (pin "1") (pinfunction "1_1") (pintype "passive"))
      (node (ref "E1") (pin "10") (pinfunction "VCC_10") (pintype "passive"))
      (node (ref "E2") (pin "6") (pinfunction "VCC_6") (pintype "passive"))
      (node (ref "IC1") (pin "4") (pinfunction "FB_4") (pintype "input"))
      (node (ref "J10") (pin "1") (pinfunction "1_1") (pintype "bidirectional"))
      (node (ref "J9") (pin "1") (pinfunction "VBUS_1") (pintype "bidirectional"))
      (node (ref "JTAG1") (pin "6") (pinfunction "6_6") (pintype "bidirectional"))
      (node (ref "L1") (pin "2") (pinfunction "2_2") (pintype "passive"))
      (node (ref "R11") (pin "2") (pinfunction "2_2") (pintype "passive"))
      (node (ref "R12") (pin "2") (pinfunction "2_2") (pintype "passive"))
      (node (ref "R17") (pin "1") (pinfunction "1_1") (pintype "passive"))
      (node (ref "T1") (pin "1") (pinfunction "1_1") (pintype "passive"))
      (node (ref "T3") (pin "2") (pinfunction "S_2") (pintype "passive"))
      (node (ref "U1") (pin "10") (pinfunction "VCC_10") (pintype "power_in"))
      (node (ref "U1") (pin "100") (pinfunction "AVCC_100") (pintype "power_in"))
      (node (ref "U1") (pin "31") (pinfunction "VCC_31") (pintype "power_in"))
      (node (ref "U1") (pin "61") (pinfunction "VCC_61") (pintype "power_in"))
      (node (ref "U1") (pin "80") (pinfunction "VCC_80") (pintype "power_in"))
    )
    (net (code "50") (name "VCC_Sensor") (class "Default")
      (node (ref "C10") (pin "2") (pinfunction "2_2") (pintype "passive"))
      (node (ref "C16") (pin "2") (pinfunction "2_2") (pintype "passive"))
      (node (ref "C3") (pin "1") (pinfunction "1_1") (pintype "passive"))
      (node (ref "C7") (pin "1") (pinfunction "1_1") (pintype "passive"))
      (node (ref "C9") (pin "2") (pinfunction "2_2") (pintype "passive"))
      (node (ref "J1") (pin "1") (pinfunction "1_1") (pintype "passive"))
      (node (ref "J2") (pin "3") (pinfunction "3_3") (pintype "passive"))
      (node (ref "J3") (pin "1") (pinfunction "1_1") (pintype "passive"))
      (node (ref "J4") (pin "1") (pinfunction "1_1") (pintype "passive"))
      (node (ref "J5") (pin "1") (pinfunction "1_1") (pintype "passive"))
      (node (ref "J6") (pin "3") (pinfunction "3_3") (pintype "passive"))
      (node (ref "J7") (pin "1") (pinfunction "1_1") (pintype "passive"))
      (node (ref "J8") (pin "1") (pinfunction "1_1") (pintype "passive"))
      (node (ref "R1") (pin "2") (pinfunction "2_2") (pintype "passive"))
      (node (ref "R4") (pin "1") (pinfunction "1_1") (pintype "passive"))
      (node (ref "R5") (pin "2") (pinfunction "2_2") (pintype "passive"))
      (node (ref "R6") (pin "1") (pinfunction "1_1") (pintype "passive"))
      (node (ref "T3") (pin "3") (pinfunction "D_3") (pintype "passive"))
      (node (ref "T4") (pin "1") (pinfunction "1_1") (pintype "passive"))
    )
    (net (code "51") (name "VSOLAR") (class "Default")
      (node (ref "J12") (pin "1") (pinfunction "1_1") (pintype "passive"))
      (node (ref "J14") (pin "2") (pinfunction "POS_2") (pintype "passive"))
      (node (ref "T5") (pin "1") (pinfunction "1_1") (pintype "passive"))
    )
    (net (code "52") (name "unconnected-(E1-ANT-Pad21)") (class "Default")
      (node (ref "E1") (pin "21") (pinfunction "ANT_21") (pintype "passive"))
    )
    (net (code "53") (name "unconnected-(E1-GND-Pad11)") (class "Default")
      (node (ref "E1") (pin "11") (pinfunction "GND_11") (pintype "passive"))
    )
    (net (code "54") (name "unconnected-(E1-NC-Pad12)") (class "Default")
      (node (ref "E1") (pin "12") (pinfunction "NC_12") (pintype "passive"))
    )
    (net (code "55") (name "unconnected-(E1-NC-Pad14)") (class "Default")
      (node (ref "E1") (pin "14") (pinfunction "NC_14") (pintype "passive"))
    )
    (net (code "56") (name "unconnected-(E1-NC-Pad15)") (class "Default")
      (node (ref "E1") (pin "15") (pinfunction "NC_15") (pintype "passive"))
    )
    (net (code "57") (name "unconnected-(E1-NC-Pad16)") (class "Default")
      (node (ref "E1") (pin "16") (pinfunction "NC_16") (pintype "passive"))
    )
    (net (code "58") (name "unconnected-(E1-NC-Pad17)") (class "Default")
      (node (ref "E1") (pin "17") (pinfunction "NC_17") (pintype "passive"))
    )
    (net (code "59") (name "unconnected-(E1-NC-Pad18)") (class "Default")
      (node (ref "E1") (pin "18") (pinfunction "NC_18") (pintype "passive"))
    )
    (net (code "60") (name "unconnected-(E2-3.3V-Pad11)") (class "Default")
      (node (ref "E2") (pin "11") (pinfunction "3.3V_11") (pintype "passive"))
    )
    (net (code "61") (name "unconnected-(E2-ANT-Pad18)") (class "Default")
      (node (ref "E2") (pin "18") (pinfunction "ANT_18") (pintype "passive"))
    )
    (net (code "62") (name "unconnected-(E2-PB0-Pad14)") (class "Default")
      (node (ref "E2") (pin "14") (pinfunction "PB0_14") (pintype "passive"))
    )
    (net (code "63") (name "unconnected-(E2-PB1-Pad13)") (class "Default")
      (node (ref "E2") (pin "13") (pinfunction "PB1_13") (pintype "passive"))
    )
    (net (code "64") (name "unconnected-(E2-PB3-Pad12)") (class "Default")
      (node (ref "E2") (pin "12") (pinfunction "PB3_12") (pintype "passive"))
    )
    (net (code "65") (name "unconnected-(E2-SWIM-Pad10)") (class "Default")
      (node (ref "E2") (pin "10") (pinfunction "SWIM_10") (pintype "passive"))
    )
    (net (code "66") (name "unconnected-(J9-+D-Pad3)") (class "Default")
      (node (ref "J9") (pin "3") (pinfunction "+D_3") (pintype "bidirectional"))
    )
    (net (code "67") (name "unconnected-(J9--D-Pad2)") (class "Default")
      (node (ref "J9") (pin "2") (pinfunction "-D_2") (pintype "bidirectional"))
    )
    (net (code "68") (name "unconnected-(J9-SH-Pad5)") (class "Default")
      (node (ref "J9") (pin "5") (pinfunction "SH_5") (pintype "power_in"))
    )
    (net (code "69") (name "unconnected-(JTAG1-Pad9)") (class "Default")
      (node (ref "JTAG1") (pin "9") (pinfunction "9_9") (pintype "bidirectional"))
    )
    (net (code "70") (name "unconnected-(JTAG1-Pad10)") (class "Default")
      (node (ref "JTAG1") (pin "10") (pinfunction "10_10") (pintype "bidirectional"))
    )
    (net (code "71") (name "unconnected-(U1-PA0_(AD0)-Pad78)") (class "Default")
      (node (ref "U1") (pin "78") (pinfunction "PA0_(AD0)_78") (pintype "bidirectional"))
    )
    (net (code "72") (name "unconnected-(U1-PA1_(AD1)-Pad77)") (class "Default")
      (node (ref "U1") (pin "77") (pinfunction "PA1_(AD1)_77") (pintype "bidirectional"))
    )
    (net (code "73") (name "unconnected-(U1-PA2_(AD2)-Pad76)") (class "Default")
      (node (ref "U1") (pin "76") (pinfunction "PA2_(AD2)_76") (pintype "bidirectional"))
    )
    (net (code "74") (name "unconnected-(U1-PA3_(AD3)-Pad75)") (class "Default")
      (node (ref "U1") (pin "75") (pinfunction "PA3_(AD3)_75") (pintype "bidirectional"))
    )
    (net (code "75") (name "unconnected-(U1-PA4_(AD4)-Pad74)") (class "Default")
      (node (ref "U1") (pin "74") (pinfunction "PA4_(AD4)_74") (pintype "bidirectional"))
    )
    (net (code "76") (name "unconnected-(U1-PA5_(AD5)-Pad73)") (class "Default")
      (node (ref "U1") (pin "73") (pinfunction "PA5_(AD5)_73") (pintype "bidirectional"))
    )
    (net (code "77") (name "unconnected-(U1-PA6_(AD6)-Pad72)") (class "Default")
      (node (ref "U1") (pin "72") (pinfunction "PA6_(AD6)_72") (pintype "bidirectional"))
    )
    (net (code "78") (name "unconnected-(U1-PA7_(AD7)-Pad71)") (class "Default")
      (node (ref "U1") (pin "71") (pinfunction "PA7_(AD7)_71") (pintype "bidirectional"))
    )
    (net (code "79") (name "unconnected-(U1-PB0_(~{SS}{slash}PCINT0)-Pad19)") (class "Default")
      (node (ref "U1") (pin "19") (pinfunction "PB0_(~{SS}/PCINT0)_19") (pintype "bidirectional"))
    )
    (net (code "80") (name "unconnected-(U1-PB4_(OC2A{slash}PCINT4)-Pad23)") (class "Default")
      (node (ref "U1") (pin "23") (pinfunction "PB4_(OC2A/PCINT4)_23") (pintype "bidirectional"))
    )
    (net (code "81") (name "unconnected-(U1-PB5_(OC1A{slash}PCINT5)-Pad24)") (class "Default")
      (node (ref "U1") (pin "24") (pinfunction "PB5_(OC1A/PCINT5)_24") (pintype "bidirectional"))
    )
    (net (code "82") (name "unconnected-(U1-PB6_(OC1B{slash}PCINT6)-Pad25)") (class "Default")
      (node (ref "U1") (pin "25") (pinfunction "PB6_(OC1B/PCINT6)_25") (pintype "bidirectional"))
    )
    (net (code "83") (name "unconnected-(U1-PB7_(OC0A{slash}OC1C{slash}PCINT7)-Pad26)") (class "Default")
      (node (ref "U1") (pin "26") (pinfunction "PB7_(OC0A/OC1C/PCINT7)_26") (pintype "bidirectional"))
    )
    (net (code "84") (name "unconnected-(U1-PC3_(A11)-Pad56)") (class "Default")
      (node (ref "U1") (pin "56") (pinfunction "PC3_(A11)_56") (pintype "bidirectional"))
    )
    (net (code "85") (name "unconnected-(U1-PC6_(A14)-Pad59)") (class "Default")
      (node (ref "U1") (pin "59") (pinfunction "PC6_(A14)_59") (pintype "bidirectional"))
    )
    (net (code "86") (name "unconnected-(U1-PC7_(A15)-Pad60)") (class "Default")
      (node (ref "U1") (pin "60") (pinfunction "PC7_(A15)_60") (pintype "bidirectional"))
    )
    (net (code "87") (name "unconnected-(U1-PD2_(RXD1{slash}INT2)-Pad45)") (class "Default")
      (node (ref "U1") (pin "45") (pinfunction "PD2_(RXD1/INT2)_45") (pintype "bidirectional"))
    )
    (net (code "88") (name "unconnected-(U1-PD3_(TXD1{slash}INT3)-Pad46)") (class "Default")
      (node (ref "U1") (pin "46") (pinfunction "PD3_(TXD1/INT3)_46") (pintype "bidirectional"))
    )
    (net (code "89") (name "unconnected-(U1-PD4_(ICP1)-Pad47)") (class "Default")
      (node (ref "U1") (pin "47") (pinfunction "PD4_(ICP1)_47") (pintype "bidirectional"))
    )
    (net (code "90") (name "unconnected-(U1-PD5_(XCK1)-Pad48)") (class "Default")
      (node (ref "U1") (pin "48") (pinfunction "PD5_(XCK1)_48") (pintype "bidirectional"))
    )
    (net (code "91") (name "unconnected-(U1-PD6_(T1)-Pad49)") (class "Default")
      (node (ref "U1") (pin "49") (pinfunction "PD6_(T1)_49") (pintype "bidirectional"))
    )
    (net (code "92") (name "unconnected-(U1-PE2_(XCK0{slash}AIN0)-Pad4)") (class "Default")
      (node (ref "U1") (pin "4") (pinfunction "PE2_(XCK0/AIN0)_4") (pintype "bidirectional"))
    )
    (net (code "93") (name "unconnected-(U1-PE6_(T3{slash}INT6)-Pad8)") (class "Default")
      (node (ref "U1") (pin "8") (pinfunction "PE6_(T3/INT6)_8") (pintype "bidirectional"))
    )
    (net (code "94") (name "unconnected-(U1-PE7_(CLKO{slash}ICP3{slash}INT7)-Pad9)") (class "Default")
      (node (ref "U1") (pin "9") (pinfunction "PE7_(CLKO/ICP3/INT7)_9") (pintype "bidirectional"))
    )
    (net (code "95") (name "unconnected-(U1-PF4_(ADC4{slash}TCK)-Pad93)") (class "Default")
      (node (ref "U1") (pin "93") (pinfunction "PF4_(ADC4/TCK)_93") (pintype "bidirectional"))
    )
    (net (code "96") (name "unconnected-(U1-PF5_(ADC5{slash}TMS)-Pad92)") (class "Default")
      (node (ref "U1") (pin "92") (pinfunction "PF5_(ADC5/TMS)_92") (pintype "bidirectional"))
    )
    (net (code "97") (name "unconnected-(U1-PF7_(ADC7{slash}TDI)-Pad90)") (class "Default")
      (node (ref "U1") (pin "90") (pinfunction "PF7_(ADC7/TDI)_90") (pintype "bidirectional"))
    )
    (net (code "98") (name "unconnected-(U1-PG1_(RD)-Pad52)") (class "Default")
      (node (ref "U1") (pin "52") (pinfunction "PG1_(RD)_52") (pintype "bidirectional"))
    )
    (net (code "99") (name "unconnected-(U1-PG2_(ALE)-Pad70)") (class "Default")
      (node (ref "U1") (pin "70") (pinfunction "PG2_(ALE)_70") (pintype "bidirectional"))
    )
    (net (code "100") (name "unconnected-(U1-PG3_(TOSC2)-Pad28)") (class "Default")
      (node (ref "U1") (pin "28") (pinfunction "PG3_(TOSC2)_28") (pintype "bidirectional"))
    )
    (net (code "101") (name "unconnected-(U1-PG4_(TOSC1)-Pad29)") (class "Default")
      (node (ref "U1") (pin "29") (pinfunction "PG4_(TOSC1)_29") (pintype "bidirectional"))
    )
    (net (code "102") (name "unconnected-(U1-PG5_(OC0B)-Pad1)") (class "Default")
      (node (ref "U1") (pin "1") (pinfunction "PG5_(OC0B)_1") (pintype "bidirectional"))
    )
    (net (code "103") (name "unconnected-(U1-PH2_(XCK2)-Pad14)") (class "Default")
      (node (ref "U1") (pin "14") (pinfunction "PH2_(XCK2)_14") (pintype "bidirectional"))
    )
    (net (code "104") (name "unconnected-(U1-PH6_(OC2B)-Pad18)") (class "Default")
      (node (ref "U1") (pin "18") (pinfunction "PH6_(OC2B)_18") (pintype "bidirectional"))
    )
    (net (code "105") (name "unconnected-(U1-PH7_(T4)-Pad27)") (class "Default")
      (node (ref "U1") (pin "27") (pinfunction "PH7_(T4)_27") (pintype "bidirectional"))
    )
    (net (code "106") (name "unconnected-(U1-PJ0_(RXD3{slash}PCINT9)-Pad63)") (class "Default")
      (node (ref "U1") (pin "63") (pinfunction "PJ0_(RXD3/PCINT9)_63") (pintype "bidirectional"))
    )
    (net (code "107") (name "unconnected-(U1-PJ1_(TXD3{slash}PCINT10)-Pad64)") (class "Default")
      (node (ref "U1") (pin "64") (pinfunction "PJ1_(TXD3/PCINT10)_64") (pintype "bidirectional"))
    )
    (net (code "108") (name "unconnected-(U1-PJ2_(XCK3{slash}PCINT11)-Pad65)") (class "Default")
      (node (ref "U1") (pin "65") (pinfunction "PJ2_(XCK3/PCINT11)_65") (pintype "bidirectional"))
    )
    (net (code "109") (name "unconnected-(U1-PJ3_(PCINT12)-Pad66)") (class "Default")
      (node (ref "U1") (pin "66") (pinfunction "PJ3_(PCINT12)_66") (pintype "bidirectional"))
    )
    (net (code "110") (name "unconnected-(U1-PJ4_(PCINT13)-Pad67)") (class "Default")
      (node (ref "U1") (pin "67") (pinfunction "PJ4_(PCINT13)_67") (pintype "bidirectional"))
    )
    (net (code "111") (name "unconnected-(U1-PJ5_(PCINT14)-Pad68)") (class "Default")
      (node (ref "U1") (pin "68") (pinfunction "PJ5_(PCINT14)_68") (pintype "bidirectional"))
    )
    (net (code "112") (name "unconnected-(U1-PJ6_(PCINT15)-Pad69)") (class "Default")
      (node (ref "U1") (pin "69") (pinfunction "PJ6_(PCINT15)_69") (pintype "bidirectional"))
    )
    (net (code "113") (name "unconnected-(U1-PJ7-Pad79)") (class "Default")
      (node (ref "U1") (pin "79") (pinfunction "PJ7_79") (pintype "bidirectional"))
    )
    (net (code "114") (name "unconnected-(U1-PK0_(ADC8{slash}PCINT16)-Pad89)") (class "Default")
      (node (ref "U1") (pin "89") (pinfunction "PK0_(ADC8/PCINT16)_89") (pintype "bidirectional"))
    )
    (net (code "115") (name "unconnected-(U1-PK1_(ADC9{slash}PCINT17)-Pad88)") (class "Default")
      (node (ref "U1") (pin "88") (pinfunction "PK1_(ADC9/PCINT17)_88") (pintype "bidirectional"))
    )
    (net (code "116") (name "unconnected-(U1-PK2_(ADC10{slash}PCINT18)-Pad87)") (class "Default")
      (node (ref "U1") (pin "87") (pinfunction "PK2_(ADC10/PCINT18)_87") (pintype "bidirectional"))
    )
    (net (code "117") (name "unconnected-(U1-PK3_(ADC11{slash}PCINT19)-Pad86)") (class "Default")
      (node (ref "U1") (pin "86") (pinfunction "PK3_(ADC11/PCINT19)_86") (pintype "bidirectional"))
    )
    (net (code "118") (name "unconnected-(U1-PK4_(ADC12{slash}PCINT20)-Pad85)") (class "Default")
      (node (ref "U1") (pin "85") (pinfunction "PK4_(ADC12/PCINT20)_85") (pintype "bidirectional"))
    )
    (net (code "119") (name "unconnected-(U1-PK5_(ADC13{slash}PCINT21)-Pad84)") (class "Default")
      (node (ref "U1") (pin "84") (pinfunction "PK5_(ADC13/PCINT21)_84") (pintype "bidirectional"))
    )
    (net (code "120") (name "unconnected-(U1-PK6_(ADC14{slash}PCINT22)-Pad83)") (class "Default")
      (node (ref "U1") (pin "83") (pinfunction "PK6_(ADC14/PCINT22)_83") (pintype "bidirectional"))
    )
    (net (code "121") (name "unconnected-(U1-PK7_(ADC15{slash}PCINT23)-Pad82)") (class "Default")
      (node (ref "U1") (pin "82") (pinfunction "PK7_(ADC15/PCINT23)_82") (pintype "bidirectional"))
    )
    (net (code "122") (name "unconnected-(U1-PL0_(ICP4)-Pad35)") (class "Default")
      (node (ref "U1") (pin "35") (pinfunction "PL0_(ICP4)_35") (pintype "bidirectional"))
    )
    (net (code "123") (name "unconnected-(U1-PL1_(ICP5)-Pad36)") (class "Default")
      (node (ref "U1") (pin "36") (pinfunction "PL1_(ICP5)_36") (pintype "bidirectional"))
    )
    (net (code "124") (name "unconnected-(U1-PL2_(T5)-Pad37)") (class "Default")
      (node (ref "U1") (pin "37") (pinfunction "PL2_(T5)_37") (pintype "bidirectional"))
    )
    (net (code "125") (name "unconnected-(U1-PL3_(OC5A)-Pad38)") (class "Default")
      (node (ref "U1") (pin "38") (pinfunction "PL3_(OC5A)_38") (pintype "bidirectional"))
    )
  )
)
